# New_Project_2023-08-31_08-25-03.net
KiCad netlist of a schematic drawn in EasyEDA Pro
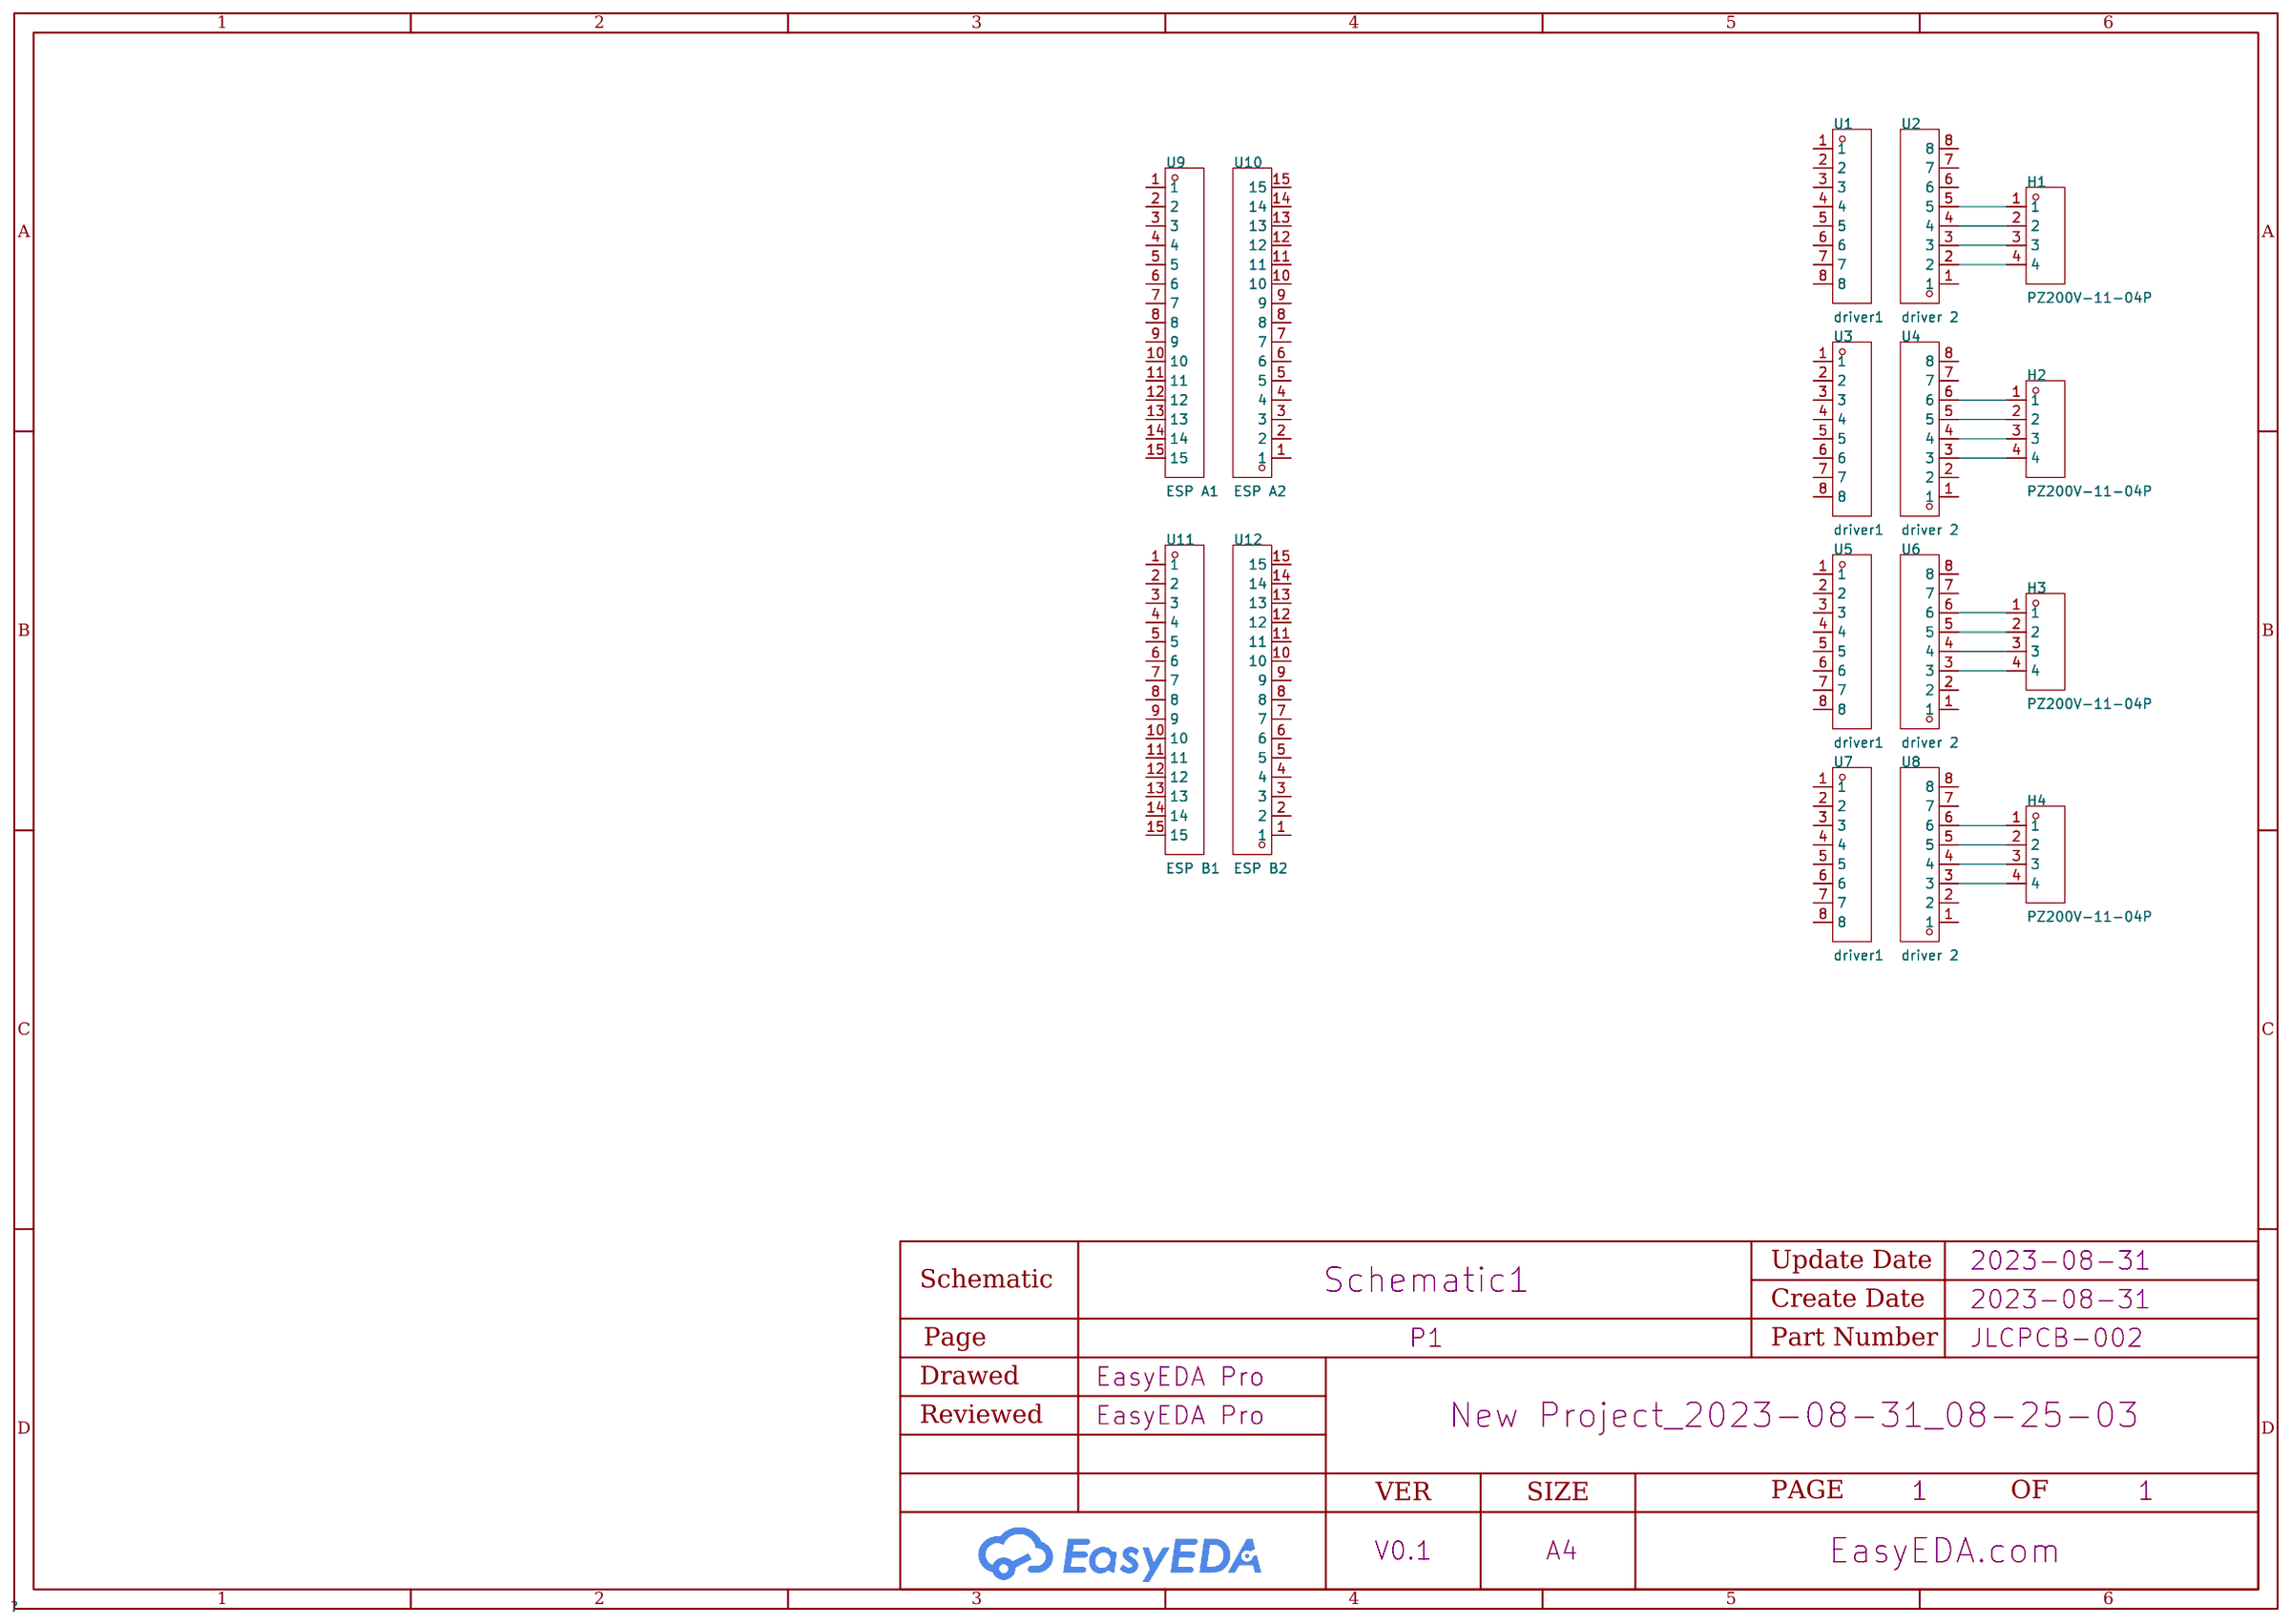
[diagram p0: schematic sheet]

(export (version "E")
  (design (tool "Eeschema 10.0.6"))
  (components
    (comp (ref "H1")
      (value "PZ200V-11-04P")
      (footprint "easyedapro:HDR-TH_4P-P2.00-V-M")
      (fields (field (name "Manufacturer") "XFCN(兴飞)"))
      (libsource (lib "easyedapro") (part "PZ200V-11-04P"))
    )
    (comp (ref "H2")
      (value "PZ200V-11-04P")
      (footprint "easyedapro:HDR-TH_4P-P2.00-V-M")
      (fields (field (name "Manufacturer") "XFCN(兴飞)"))
      (libsource (lib "easyedapro") (part "PZ200V-11-04P"))
    )
    (comp (ref "H3")
      (value "PZ200V-11-04P")
      (footprint "easyedapro:HDR-TH_4P-P2.00-V-M")
      (fields (field (name "Manufacturer") "XFCN(兴飞)"))
      (libsource (lib "easyedapro") (part "PZ200V-11-04P"))
    )
    (comp (ref "H4")
      (value "PZ200V-11-04P")
      (footprint "easyedapro:HDR-TH_4P-P2.00-V-M")
      (fields (field (name "Manufacturer") "XFCN(兴飞)"))
      (libsource (lib "easyedapro") (part "PZ200V-11-04P"))
    )
    (comp (ref "U1")
      (value "driver1")
      (footprint "easyedapro:HDR-TH_8P-P2.54-V-F")
      (fields (field (name "Manufacturer") "Liansheng(连盛)"))
      (libsource (lib "easyedapro") (part "FH-00882"))
    )
    (comp (ref "U2")
      (value "driver 2")
      (footprint "easyedapro:HDR-TH_8P-P2.54-V-F")
      (fields (field (name "Manufacturer") "Liansheng(连盛)"))
      (libsource (lib "easyedapro") (part "FH-00882"))
    )
    (comp (ref "U3")
      (value "driver1")
      (footprint "easyedapro:HDR-TH_8P-P2.54-V-F")
      (fields (field (name "Manufacturer") "Liansheng(连盛)"))
      (libsource (lib "easyedapro") (part "FH-00882"))
    )
    (comp (ref "U4")
      (value "driver 2")
      (footprint "easyedapro:HDR-TH_8P-P2.54-V-F")
      (fields (field (name "Manufacturer") "Liansheng(连盛)"))
      (libsource (lib "easyedapro") (part "FH-00882"))
    )
    (comp (ref "U5")
      (value "driver1")
      (footprint "easyedapro:HDR-TH_8P-P2.54-V-F")
      (fields (field (name "Manufacturer") "Liansheng(连盛)"))
      (libsource (lib "easyedapro") (part "FH-00882"))
    )
    (comp (ref "U6")
      (value "driver 2")
      (footprint "easyedapro:HDR-TH_8P-P2.54-V-F")
      (fields (field (name "Manufacturer") "Liansheng(连盛)"))
      (libsource (lib "easyedapro") (part "FH-00882"))
    )
    (comp (ref "U7")
      (value "driver1")
      (footprint "easyedapro:HDR-TH_8P-P2.54-V-F")
      (fields (field (name "Manufacturer") "Liansheng(连盛)"))
      (libsource (lib "easyedapro") (part "FH-00882"))
    )
    (comp (ref "U8")
      (value "driver 2")
      (footprint "easyedapro:HDR-TH_8P-P2.54-V-F")
      (fields (field (name "Manufacturer") "Liansheng(连盛)"))
      (libsource (lib "easyedapro") (part "FH-00882"))
    )
    (comp (ref "U9")
      (value "ESP A1")
      (footprint "easyedapro:HDR-TH_15P-P2.54-V-F")
      (fields (field (name "Manufacturer") "ZHOURI(洲日)"))
      (libsource (lib "easyedapro") (part "PM2.54-1*15"))
    )
    (comp (ref "U10")
      (value "ESP A2")
      (footprint "easyedapro:HDR-TH_15P-P2.54-V-F")
      (fields (field (name "Manufacturer") "ZHOURI(洲日)"))
      (libsource (lib "easyedapro") (part "PM2.54-1*15"))
    )
    (comp (ref "U11")
      (value "ESP B1")
      (footprint "easyedapro:HDR-TH_15P-P2.54-V-F")
      (fields (field (name "Manufacturer") "ZHOURI(洲日)"))
      (libsource (lib "easyedapro") (part "PM2.54-1*15"))
    )
    (comp (ref "U12")
      (value "ESP B2")
      (footprint "easyedapro:HDR-TH_15P-P2.54-V-F")
      (fields (field (name "Manufacturer") "ZHOURI(洲日)"))
      (libsource (lib "easyedapro") (part "PM2.54-1*15"))
    )
  )
  (nets
    (net (code "1") (name "Net-(H1-Pad1)") (class "Default")
      (node (ref "H1") (pin "1") (pinfunction "1_1") (pintype "input"))
      (node (ref "U2") (pin "5") (pinfunction "5_5") (pintype "input"))
    )
    (net (code "2") (name "Net-(H1-Pad2)") (class "Default")
      (node (ref "H1") (pin "2") (pinfunction "2_2") (pintype "input"))
      (node (ref "U2") (pin "4") (pinfunction "4_4") (pintype "input"))
    )
    (net (code "3") (name "Net-(H1-Pad3)") (class "Default")
      (node (ref "H1") (pin "3") (pinfunction "3_3") (pintype "input"))
      (node (ref "U2") (pin "3") (pinfunction "3_3") (pintype "input"))
    )
    (net (code "4") (name "Net-(H1-Pad4)") (class "Default")
      (node (ref "H1") (pin "4") (pinfunction "4_4") (pintype "input"))
      (node (ref "U2") (pin "2") (pinfunction "2_2") (pintype "input"))
    )
    (net (code "5") (name "Net-(H2-Pad1)") (class "Default")
      (node (ref "H2") (pin "1") (pinfunction "1_1") (pintype "input"))
      (node (ref "U4") (pin "6") (pinfunction "6_6") (pintype "input"))
    )
    (net (code "6") (name "Net-(H2-Pad2)") (class "Default")
      (node (ref "H2") (pin "2") (pinfunction "2_2") (pintype "input"))
      (node (ref "U4") (pin "5") (pinfunction "5_5") (pintype "input"))
    )
    (net (code "7") (name "Net-(H2-Pad3)") (class "Default")
      (node (ref "H2") (pin "3") (pinfunction "3_3") (pintype "input"))
      (node (ref "U4") (pin "4") (pinfunction "4_4") (pintype "input"))
    )
    (net (code "8") (name "Net-(H2-Pad4)") (class "Default")
      (node (ref "H2") (pin "4") (pinfunction "4_4") (pintype "input"))
      (node (ref "U4") (pin "3") (pinfunction "3_3") (pintype "input"))
    )
    (net (code "9") (name "Net-(H3-Pad1)") (class "Default")
      (node (ref "H3") (pin "1") (pinfunction "1_1") (pintype "input"))
      (node (ref "U6") (pin "6") (pinfunction "6_6") (pintype "input"))
    )
    (net (code "10") (name "Net-(H3-Pad2)") (class "Default")
      (node (ref "H3") (pin "2") (pinfunction "2_2") (pintype "input"))
      (node (ref "U6") (pin "5") (pinfunction "5_5") (pintype "input"))
    )
    (net (code "11") (name "Net-(H3-Pad3)") (class "Default")
      (node (ref "H3") (pin "3") (pinfunction "3_3") (pintype "input"))
      (node (ref "U6") (pin "4") (pinfunction "4_4") (pintype "input"))
    )
    (net (code "12") (name "Net-(H3-Pad4)") (class "Default")
      (node (ref "H3") (pin "4") (pinfunction "4_4") (pintype "input"))
      (node (ref "U6") (pin "3") (pinfunction "3_3") (pintype "input"))
    )
    (net (code "13") (name "Net-(H4-Pad1)") (class "Default")
      (node (ref "H4") (pin "1") (pinfunction "1_1") (pintype "input"))
      (node (ref "U8") (pin "6") (pinfunction "6_6") (pintype "input"))
    )
    (net (code "14") (name "Net-(H4-Pad2)") (class "Default")
      (node (ref "H4") (pin "2") (pinfunction "2_2") (pintype "input"))
      (node (ref "U8") (pin "5") (pinfunction "5_5") (pintype "input"))
    )
    (net (code "15") (name "Net-(H4-Pad3)") (class "Default")
      (node (ref "H4") (pin "3") (pinfunction "3_3") (pintype "input"))
      (node (ref "U8") (pin "4") (pinfunction "4_4") (pintype "input"))
    )
    (net (code "16") (name "Net-(H4-Pad4)") (class "Default")
      (node (ref "H4") (pin "4") (pinfunction "4_4") (pintype "input"))
      (node (ref "U8") (pin "3") (pinfunction "3_3") (pintype "input"))
    )
    (net (code "17") (name "unconnected-(U1-Pad1)") (class "Default")
      (node (ref "U1") (pin "1") (pinfunction "1_1") (pintype "input"))
    )
    (net (code "18") (name "unconnected-(U1-Pad2)") (class "Default")
      (node (ref "U1") (pin "2") (pinfunction "2_2") (pintype "input"))
    )
    (net (code "19") (name "unconnected-(U1-Pad3)") (class "Default")
      (node (ref "U1") (pin "3") (pinfunction "3_3") (pintype "input"))
    )
    (net (code "20") (name "unconnected-(U1-Pad4)") (class "Default")
      (node (ref "U1") (pin "4") (pinfunction "4_4") (pintype "input"))
    )
    (net (code "21") (name "unconnected-(U1-Pad5)") (class "Default")
      (node (ref "U1") (pin "5") (pinfunction "5_5") (pintype "input"))
    )
    (net (code "22") (name "unconnected-(U1-Pad6)") (class "Default")
      (node (ref "U1") (pin "6") (pinfunction "6_6") (pintype "input"))
    )
    (net (code "23") (name "unconnected-(U1-Pad7)") (class "Default")
      (node (ref "U1") (pin "7") (pinfunction "7_7") (pintype "input"))
    )
    (net (code "24") (name "unconnected-(U1-Pad8)") (class "Default")
      (node (ref "U1") (pin "8") (pinfunction "8_8") (pintype "input"))
    )
    (net (code "25") (name "unconnected-(U2-Pad1)") (class "Default")
      (node (ref "U2") (pin "1") (pinfunction "1_1") (pintype "input"))
    )
    (net (code "26") (name "unconnected-(U2-Pad6)") (class "Default")
      (node (ref "U2") (pin "6") (pinfunction "6_6") (pintype "input"))
    )
    (net (code "27") (name "unconnected-(U2-Pad7)") (class "Default")
      (node (ref "U2") (pin "7") (pinfunction "7_7") (pintype "input"))
    )
    (net (code "28") (name "unconnected-(U2-Pad8)") (class "Default")
      (node (ref "U2") (pin "8") (pinfunction "8_8") (pintype "input"))
    )
    (net (code "29") (name "unconnected-(U3-Pad1)") (class "Default")
      (node (ref "U3") (pin "1") (pinfunction "1_1") (pintype "input"))
    )
    (net (code "30") (name "unconnected-(U3-Pad2)") (class "Default")
      (node (ref "U3") (pin "2") (pinfunction "2_2") (pintype "input"))
    )
    (net (code "31") (name "unconnected-(U3-Pad3)") (class "Default")
      (node (ref "U3") (pin "3") (pinfunction "3_3") (pintype "input"))
    )
    (net (code "32") (name "unconnected-(U3-Pad4)") (class "Default")
      (node (ref "U3") (pin "4") (pinfunction "4_4") (pintype "input"))
    )
    (net (code "33") (name "unconnected-(U3-Pad5)") (class "Default")
      (node (ref "U3") (pin "5") (pinfunction "5_5") (pintype "input"))
    )
    (net (code "34") (name "unconnected-(U3-Pad6)") (class "Default")
      (node (ref "U3") (pin "6") (pinfunction "6_6") (pintype "input"))
    )
    (net (code "35") (name "unconnected-(U3-Pad7)") (class "Default")
      (node (ref "U3") (pin "7") (pinfunction "7_7") (pintype "input"))
    )
    (net (code "36") (name "unconnected-(U3-Pad8)") (class "Default")
      (node (ref "U3") (pin "8") (pinfunction "8_8") (pintype "input"))
    )
    (net (code "37") (name "unconnected-(U4-Pad1)") (class "Default")
      (node (ref "U4") (pin "1") (pinfunction "1_1") (pintype "input"))
    )
    (net (code "38") (name "unconnected-(U4-Pad2)") (class "Default")
      (node (ref "U4") (pin "2") (pinfunction "2_2") (pintype "input"))
    )
    (net (code "39") (name "unconnected-(U4-Pad7)") (class "Default")
      (node (ref "U4") (pin "7") (pinfunction "7_7") (pintype "input"))
    )
    (net (code "40") (name "unconnected-(U4-Pad8)") (class "Default")
      (node (ref "U4") (pin "8") (pinfunction "8_8") (pintype "input"))
    )
    (net (code "41") (name "unconnected-(U5-Pad1)") (class "Default")
      (node (ref "U5") (pin "1") (pinfunction "1_1") (pintype "input"))
    )
    (net (code "42") (name "unconnected-(U5-Pad2)") (class "Default")
      (node (ref "U5") (pin "2") (pinfunction "2_2") (pintype "input"))
    )
    (net (code "43") (name "unconnected-(U5-Pad3)") (class "Default")
      (node (ref "U5") (pin "3") (pinfunction "3_3") (pintype "input"))
    )
    (net (code "44") (name "unconnected-(U5-Pad4)") (class "Default")
      (node (ref "U5") (pin "4") (pinfunction "4_4") (pintype "input"))
    )
    (net (code "45") (name "unconnected-(U5-Pad5)") (class "Default")
      (node (ref "U5") (pin "5") (pinfunction "5_5") (pintype "input"))
    )
    (net (code "46") (name "unconnected-(U5-Pad6)") (class "Default")
      (node (ref "U5") (pin "6") (pinfunction "6_6") (pintype "input"))
    )
    (net (code "47") (name "unconnected-(U5-Pad7)") (class "Default")
      (node (ref "U5") (pin "7") (pinfunction "7_7") (pintype "input"))
    )
    (net (code "48") (name "unconnected-(U5-Pad8)") (class "Default")
      (node (ref "U5") (pin "8") (pinfunction "8_8") (pintype "input"))
    )
    (net (code "49") (name "unconnected-(U6-Pad1)") (class "Default")
      (node (ref "U6") (pin "1") (pinfunction "1_1") (pintype "input"))
    )
    (net (code "50") (name "unconnected-(U6-Pad2)") (class "Default")
      (node (ref "U6") (pin "2") (pinfunction "2_2") (pintype "input"))
    )
    (net (code "51") (name "unconnected-(U6-Pad7)") (class "Default")
      (node (ref "U6") (pin "7") (pinfunction "7_7") (pintype "input"))
    )
    (net (code "52") (name "unconnected-(U6-Pad8)") (class "Default")
      (node (ref "U6") (pin "8") (pinfunction "8_8") (pintype "input"))
    )
    (net (code "53") (name "unconnected-(U7-Pad1)") (class "Default")
      (node (ref "U7") (pin "1") (pinfunction "1_1") (pintype "input"))
    )
    (net (code "54") (name "unconnected-(U7-Pad2)") (class "Default")
      (node (ref "U7") (pin "2") (pinfunction "2_2") (pintype "input"))
    )
    (net (code "55") (name "unconnected-(U7-Pad3)") (class "Default")
      (node (ref "U7") (pin "3") (pinfunction "3_3") (pintype "input"))
    )
    (net (code "56") (name "unconnected-(U7-Pad4)") (class "Default")
      (node (ref "U7") (pin "4") (pinfunction "4_4") (pintype "input"))
    )
    (net (code "57") (name "unconnected-(U7-Pad5)") (class "Default")
      (node (ref "U7") (pin "5") (pinfunction "5_5") (pintype "input"))
    )
    (net (code "58") (name "unconnected-(U7-Pad6)") (class "Default")
      (node (ref "U7") (pin "6") (pinfunction "6_6") (pintype "input"))
    )
    (net (code "59") (name "unconnected-(U7-Pad7)") (class "Default")
      (node (ref "U7") (pin "7") (pinfunction "7_7") (pintype "input"))
    )
    (net (code "60") (name "unconnected-(U7-Pad8)") (class "Default")
      (node (ref "U7") (pin "8") (pinfunction "8_8") (pintype "input"))
    )
    (net (code "61") (name "unconnected-(U8-Pad1)") (class "Default")
      (node (ref "U8") (pin "1") (pinfunction "1_1") (pintype "input"))
    )
    (net (code "62") (name "unconnected-(U8-Pad2)") (class "Default")
      (node (ref "U8") (pin "2") (pinfunction "2_2") (pintype "input"))
    )
    (net (code "63") (name "unconnected-(U8-Pad7)") (class "Default")
      (node (ref "U8") (pin "7") (pinfunction "7_7") (pintype "input"))
    )
    (net (code "64") (name "unconnected-(U8-Pad8)") (class "Default")
      (node (ref "U8") (pin "8") (pinfunction "8_8") (pintype "input"))
    )
    (net (code "65") (name "unconnected-(U9-Pad1)") (class "Default")
      (node (ref "U9") (pin "1") (pinfunction "1_1") (pintype "input"))
    )
    (net (code "66") (name "unconnected-(U9-Pad2)") (class "Default")
      (node (ref "U9") (pin "2") (pinfunction "2_2") (pintype "input"))
    )
    (net (code "67") (name "unconnected-(U9-Pad3)") (class "Default")
      (node (ref "U9") (pin "3") (pinfunction "3_3") (pintype "input"))
    )
    (net (code "68") (name "unconnected-(U9-Pad4)") (class "Default")
      (node (ref "U9") (pin "4") (pinfunction "4_4") (pintype "input"))
    )
    (net (code "69") (name "unconnected-(U9-Pad5)") (class "Default")
      (node (ref "U9") (pin "5") (pinfunction "5_5") (pintype "input"))
    )
    (net (code "70") (name "unconnected-(U9-Pad6)") (class "Default")
      (node (ref "U9") (pin "6") (pinfunction "6_6") (pintype "input"))
    )
    (net (code "71") (name "unconnected-(U9-Pad7)") (class "Default")
      (node (ref "U9") (pin "7") (pinfunction "7_7") (pintype "input"))
    )
    (net (code "72") (name "unconnected-(U9-Pad8)") (class "Default")
      (node (ref "U9") (pin "8") (pinfunction "8_8") (pintype "input"))
    )
    (net (code "73") (name "unconnected-(U9-Pad9)") (class "Default")
      (node (ref "U9") (pin "9") (pinfunction "9_9") (pintype "input"))
    )
    (net (code "74") (name "unconnected-(U9-Pad10)") (class "Default")
      (node (ref "U9") (pin "10") (pinfunction "10_10") (pintype "input"))
    )
    (net (code "75") (name "unconnected-(U9-Pad11)") (class "Default")
      (node (ref "U9") (pin "11") (pinfunction "11_11") (pintype "input"))
    )
    (net (code "76") (name "unconnected-(U9-Pad12)") (class "Default")
      (node (ref "U9") (pin "12") (pinfunction "12_12") (pintype "input"))
    )
    (net (code "77") (name "unconnected-(U9-Pad13)") (class "Default")
      (node (ref "U9") (pin "13") (pinfunction "13_13") (pintype "input"))
    )
    (net (code "78") (name "unconnected-(U9-Pad14)") (class "Default")
      (node (ref "U9") (pin "14") (pinfunction "14_14") (pintype "input"))
    )
    (net (code "79") (name "unconnected-(U9-Pad15)") (class "Default")
      (node (ref "U9") (pin "15") (pinfunction "15_15") (pintype "input"))
    )
    (net (code "80") (name "unconnected-(U10-Pad1)") (class "Default")
      (node (ref "U10") (pin "1") (pinfunction "1_1") (pintype "input"))
    )
    (net (code "81") (name "unconnected-(U10-Pad2)") (class "Default")
      (node (ref "U10") (pin "2") (pinfunction "2_2") (pintype "input"))
    )
    (net (code "82") (name "unconnected-(U10-Pad3)") (class "Default")
      (node (ref "U10") (pin "3") (pinfunction "3_3") (pintype "input"))
    )
    (net (code "83") (name "unconnected-(U10-Pad4)") (class "Default")
      (node (ref "U10") (pin "4") (pinfunction "4_4") (pintype "input"))
    )
    (net (code "84") (name "unconnected-(U10-Pad5)") (class "Default")
      (node (ref "U10") (pin "5") (pinfunction "5_5") (pintype "input"))
    )
    (net (code "85") (name "unconnected-(U10-Pad6)") (class "Default")
      (node (ref "U10") (pin "6") (pinfunction "6_6") (pintype "input"))
    )
    (net (code "86") (name "unconnected-(U10-Pad7)") (class "Default")
      (node (ref "U10") (pin "7") (pinfunction "7_7") (pintype "input"))
    )
    (net (code "87") (name "unconnected-(U10-Pad8)") (class "Default")
      (node (ref "U10") (pin "8") (pinfunction "8_8") (pintype "input"))
    )
    (net (code "88") (name "unconnected-(U10-Pad9)") (class "Default")
      (node (ref "U10") (pin "9") (pinfunction "9_9") (pintype "input"))
    )
    (net (code "89") (name "unconnected-(U10-Pad10)") (class "Default")
      (node (ref "U10") (pin "10") (pinfunction "10_10") (pintype "input"))
    )
    (net (code "90") (name "unconnected-(U10-Pad11)") (class "Default")
      (node (ref "U10") (pin "11") (pinfunction "11_11") (pintype "input"))
    )
    (net (code "91") (name "unconnected-(U10-Pad12)") (class "Default")
      (node (ref "U10") (pin "12") (pinfunction "12_12") (pintype "input"))
    )
    (net (code "92") (name "unconnected-(U10-Pad13)") (class "Default")
      (node (ref "U10") (pin "13") (pinfunction "13_13") (pintype "input"))
    )
    (net (code "93") (name "unconnected-(U10-Pad14)") (class "Default")
      (node (ref "U10") (pin "14") (pinfunction "14_14") (pintype "input"))
    )
    (net (code "94") (name "unconnected-(U10-Pad15)") (class "Default")
      (node (ref "U10") (pin "15") (pinfunction "15_15") (pintype "input"))
    )
    (net (code "95") (name "unconnected-(U11-Pad1)") (class "Default")
      (node (ref "U11") (pin "1") (pinfunction "1_1") (pintype "input"))
    )
    (net (code "96") (name "unconnected-(U11-Pad2)") (class "Default")
      (node (ref "U11") (pin "2") (pinfunction "2_2") (pintype "input"))
    )
    (net (code "97") (name "unconnected-(U11-Pad3)") (class "Default")
      (node (ref "U11") (pin "3") (pinfunction "3_3") (pintype "input"))
    )
    (net (code "98") (name "unconnected-(U11-Pad4)") (class "Default")
      (node (ref "U11") (pin "4") (pinfunction "4_4") (pintype "input"))
    )
    (net (code "99") (name "unconnected-(U11-Pad5)") (class "Default")
      (node (ref "U11") (pin "5") (pinfunction "5_5") (pintype "input"))
    )
    (net (code "100") (name "unconnected-(U11-Pad6)") (class "Default")
      (node (ref "U11") (pin "6") (pinfunction "6_6") (pintype "input"))
    )
    (net (code "101") (name "unconnected-(U11-Pad7)") (class "Default")
      (node (ref "U11") (pin "7") (pinfunction "7_7") (pintype "input"))
    )
    (net (code "102") (name "unconnected-(U11-Pad8)") (class "Default")
      (node (ref "U11") (pin "8") (pinfunction "8_8") (pintype "input"))
    )
    (net (code "103") (name "unconnected-(U11-Pad9)") (class "Default")
      (node (ref "U11") (pin "9") (pinfunction "9_9") (pintype "input"))
    )
    (net (code "104") (name "unconnected-(U11-Pad10)") (class "Default")
      (node (ref "U11") (pin "10") (pinfunction "10_10") (pintype "input"))
    )
    (net (code "105") (name "unconnected-(U11-Pad11)") (class "Default")
      (node (ref "U11") (pin "11") (pinfunction "11_11") (pintype "input"))
    )
    (net (code "106") (name "unconnected-(U11-Pad12)") (class "Default")
      (node (ref "U11") (pin "12") (pinfunction "12_12") (pintype "input"))
    )
    (net (code "107") (name "unconnected-(U11-Pad13)") (class "Default")
      (node (ref "U11") (pin "13") (pinfunction "13_13") (pintype "input"))
    )
    (net (code "108") (name "unconnected-(U11-Pad14)") (class "Default")
      (node (ref "U11") (pin "14") (pinfunction "14_14") (pintype "input"))
    )
    (net (code "109") (name "unconnected-(U11-Pad15)") (class "Default")
      (node (ref "U11") (pin "15") (pinfunction "15_15") (pintype "input"))
    )
    (net (code "110") (name "unconnected-(U12-Pad1)") (class "Default")
      (node (ref "U12") (pin "1") (pinfunction "1_1") (pintype "input"))
    )
    (net (code "111") (name "unconnected-(U12-Pad2)") (class "Default")
      (node (ref "U12") (pin "2") (pinfunction "2_2") (pintype "input"))
    )
    (net (code "112") (name "unconnected-(U12-Pad3)") (class "Default")
      (node (ref "U12") (pin "3") (pinfunction "3_3") (pintype "input"))
    )
    (net (code "113") (name "unconnected-(U12-Pad4)") (class "Default")
      (node (ref "U12") (pin "4") (pinfunction "4_4") (pintype "input"))
    )
    (net (code "114") (name "unconnected-(U12-Pad5)") (class "Default")
      (node (ref "U12") (pin "5") (pinfunction "5_5") (pintype "input"))
    )
    (net (code "115") (name "unconnected-(U12-Pad6)") (class "Default")
      (node (ref "U12") (pin "6") (pinfunction "6_6") (pintype "input"))
    )
    (net (code "116") (name "unconnected-(U12-Pad7)") (class "Default")
      (node (ref "U12") (pin "7") (pinfunction "7_7") (pintype "input"))
    )
    (net (code "117") (name "unconnected-(U12-Pad8)") (class "Default")
      (node (ref "U12") (pin "8") (pinfunction "8_8") (pintype "input"))
    )
    (net (code "118") (name "unconnected-(U12-Pad9)") (class "Default")
      (node (ref "U12") (pin "9") (pinfunction "9_9") (pintype "input"))
    )
    (net (code "119") (name "unconnected-(U12-Pad10)") (class "Default")
      (node (ref "U12") (pin "10") (pinfunction "10_10") (pintype "input"))
    )
    (net (code "120") (name "unconnected-(U12-Pad11)") (class "Default")
      (node (ref "U12") (pin "11") (pinfunction "11_11") (pintype "input"))
    )
    (net (code "121") (name "unconnected-(U12-Pad12)") (class "Default")
      (node (ref "U12") (pin "12") (pinfunction "12_12") (pintype "input"))
    )
    (net (code "122") (name "unconnected-(U12-Pad13)") (class "Default")
      (node (ref "U12") (pin "13") (pinfunction "13_13") (pintype "input"))
    )
    (net (code "123") (name "unconnected-(U12-Pad14)") (class "Default")
      (node (ref "U12") (pin "14") (pinfunction "14_14") (pintype "input"))
    )
    (net (code "124") (name "unconnected-(U12-Pad15)") (class "Default")
      (node (ref "U12") (pin "15") (pinfunction "15_15") (pintype "input"))
    )
  )
)
